# SX1262_Radio.net
KiCad netlist of a schematic drawn in Altium Designer
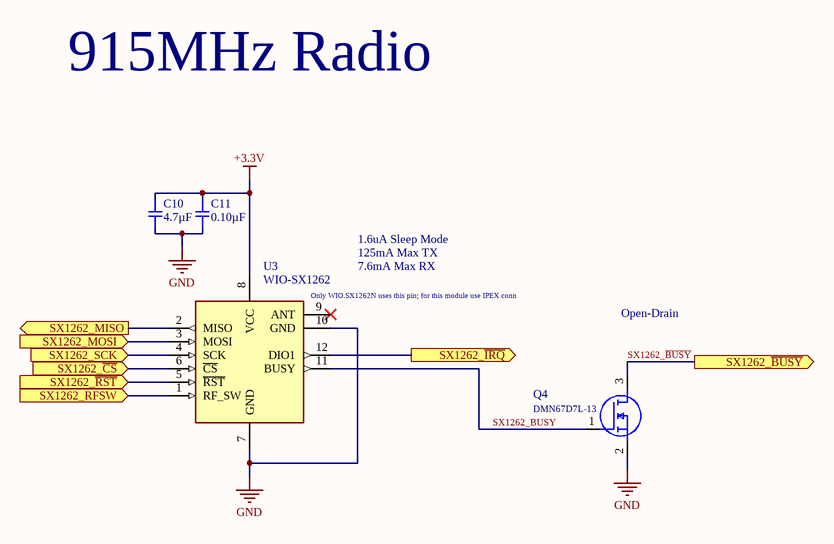
[diagram p0: SX1262_Radio.SchDoc]

(export (version "E")
  (design (tool "Eeschema 10.0.6"))
  (components
    (comp (ref "C10")
      (value "4.7µF")
      (footprint "SMD-0402C")
      (description "CAP CER 4.7UF 6.3V X5R 0402")
      (fields
        (field (name "DIGI-KEY PART NUMBER") "490-13232-1-ND")
        (field (name "PART NUMBER") "GRM153R60J475ME15D")
      )
      (libsource (lib "capacitor_murata_0402") (part "GRM153R60J475ME15D"))
    )
    (comp (ref "C11")
      (value "0.10µF")
      (footprint "SMD-0402C")
      (description "CAP CER 0.1UF 16V X7R 0402")
      (fields
        (field (name "DIGI-KEY PART NUMBER") "490-4759-1-ND")
        (field (name "PART NUMBER") "GCM155R71C104KA55D")
      )
      (libsource (lib "capacitor_murata_0402") (part "GCM155R71C104KA55D"))
    )
    (comp (ref "Q4")
      (value "DMN67D7L-13")
      (footprint "SamacSys:DMN67D7L13")
      (description "MOSFET (N-Channel)")
      (fields (field (name "MOUSER PART NUMBER") "621-DMN67D7L-13"))
      (libsource (lib "*") (part "DMN67D7L-13"))
    )
    (comp (ref "U3")
      (value "WIO-SX1262")
      (footprint "114993390")
      (fields
        (field (name "MANUFACTURER_PART_NUMBER") "114993390")
        (field (name "MOUSER PART NUMBER") "713-114993390")
      )
      (libsource (lib "SomoPowerPackControl") (part "WIO-SX1262"))
    )
  )
  (nets
    (net (code "1") (name "+3.3V") (class "Default")
      (node (ref "C10") (pin "1") (pinfunction "1_1") (pintype "passive"))
      (node (ref "C11") (pin "1") (pinfunction "1_1") (pintype "passive"))
      (node (ref "U3") (pin "8") (pinfunction "VCC_8") (pintype "passive"))
    )
    (net (code "2") (name "/SX1262_BUSY") (class "Default")
      (node (ref "Q4") (pin "1") (pinfunction "G_1") (pintype "passive"))
      (node (ref "U3") (pin "11") (pinfunction "BUSY_11") (pintype "output"))
    )
    (net (code "3") (name "/SX1262_MISO") (class "Default")
      (node (ref "U3") (pin "2") (pinfunction "MISO_2") (pintype "output"))
    )
    (net (code "4") (name "/SX1262_MOSI") (class "Default")
      (node (ref "U3") (pin "3") (pinfunction "MOSI_3") (pintype "input"))
    )
    (net (code "5") (name "/SX1262_RFSW") (class "Default")
      (node (ref "U3") (pin "1") (pinfunction "RF_SW_1") (pintype "input"))
    )
    (net (code "6") (name "/SX1262_SCK") (class "Default")
      (node (ref "U3") (pin "4") (pinfunction "SCK_4") (pintype "input"))
    )
    (net (code "7") (name "/SX1262_~{BUSY}") (class "Default")
      (node (ref "Q4") (pin "3") (pinfunction "D_3") (pintype "passive"))
    )
    (net (code "8") (name "/SX1262_~{CS}") (class "Default")
      (node (ref "U3") (pin "6") (pinfunction "~{CS}_6") (pintype "input"))
    )
    (net (code "9") (name "/SX1262_~{IRQ}") (class "Default")
      (node (ref "U3") (pin "12") (pinfunction "DIO1_12") (pintype "output"))
    )
    (net (code "10") (name "/SX1262_~{RST}") (class "Default")
      (node (ref "U3") (pin "5") (pinfunction "~{RST}_5") (pintype "input"))
    )
    (net (code "11") (name "GND") (class "Default")
      (node (ref "C10") (pin "2") (pinfunction "2_2") (pintype "passive"))
      (node (ref "C11") (pin "2") (pinfunction "2_2") (pintype "passive"))
      (node (ref "Q4") (pin "2") (pinfunction "S_2") (pintype "passive"))
      (node (ref "U3") (pin "10") (pinfunction "GND_10") (pintype "passive"))
      (node (ref "U3") (pin "7") (pinfunction "GND_7") (pintype "passive"))
    )
    (net (code "12") (name "unconnected-(U3-ANT-Pad9)") (class "Default")
      (node (ref "U3") (pin "9") (pinfunction "ANT_9") (pintype "passive+no_connect"))
    )
  )
)
